# SunlightDetector.net
KiCad netlist of a schematic drawn in EAGLE
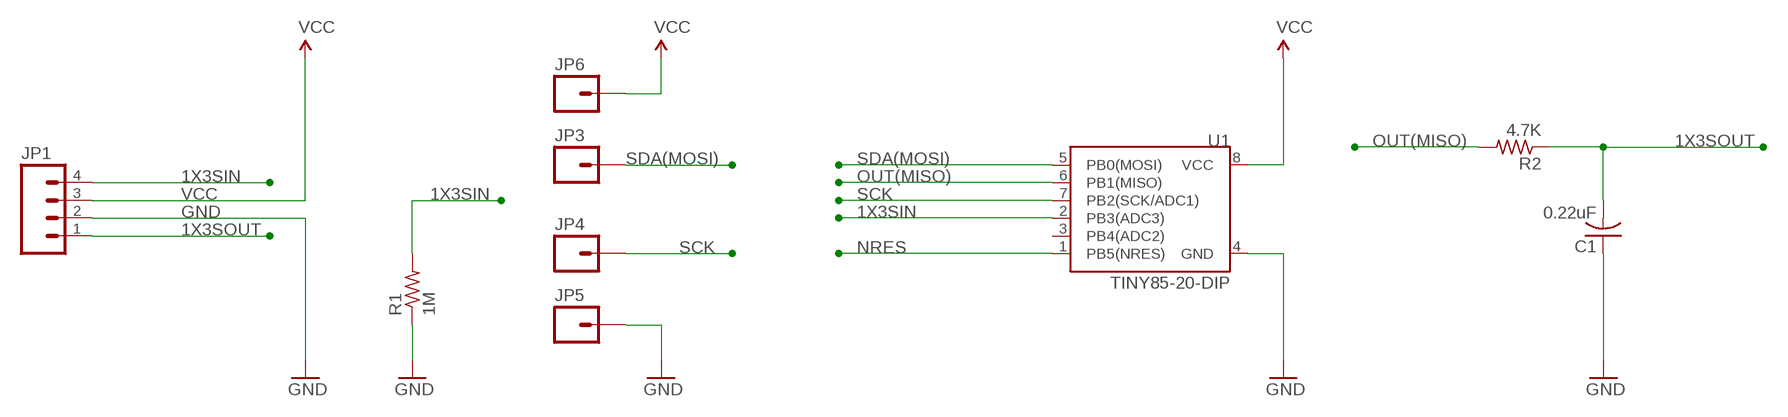
[diagram p0: schematic, sheet 1]

(export (version "E")
  (design (tool "Eeschema 10.0.6"))
  (components
    (comp (ref "C1")
      (value "0.22uF")
      (footprint "eagle-import:C0402")
      (libsource (lib "eagle-import") (part "C-USC0402"))
    )
    (comp (ref "JP1")
      (value "M04PTH")
      (footprint "eagle-import:1X04")
      (libsource (lib "eagle-import") (part "M04PTH"))
    )
    (comp (ref "JP3")
      (value "M01PTH")
      (footprint "eagle-import:1X01")
      (libsource (lib "eagle-import") (part "M01PTH"))
    )
    (comp (ref "JP4")
      (value "M01PTH")
      (footprint "eagle-import:1X01")
      (libsource (lib "eagle-import") (part "M01PTH"))
    )
    (comp (ref "JP5")
      (value "M01PTH")
      (footprint "eagle-import:1X01")
      (libsource (lib "eagle-import") (part "M01PTH"))
    )
    (comp (ref "JP6")
      (value "M01PTH")
      (footprint "eagle-import:1X01")
      (libsource (lib "eagle-import") (part "M01PTH"))
    )
    (comp (ref "R1")
      (value "1M")
      (footprint "eagle-import:R0603")
      (libsource (lib "eagle-import") (part "R-US_R0603"))
    )
    (comp (ref "R2")
      (value "4.7K")
      (footprint "eagle-import:R0603")
      (libsource (lib "eagle-import") (part "R-US_R0603"))
    )
    (comp (ref "U1")
      (value "TINY85-20-DIP")
      (footprint "eagle-import:DIP08")
      (libsource (lib "eagle-import") (part "ATTINY45TINY85-20-DIP"))
    )
  )
  (nets
    (net (code "1") (name "/1X3SIN") (class "Default")
      (node (ref "JP1") (pin "4") (pinfunction "4_4") (pintype "passive"))
      (node (ref "R1") (pin "2") (pinfunction "2_2") (pintype "passive"))
      (node (ref "U1") (pin "2") (pinfunction "PB3(ADC3)_2") (pintype "bidirectional"))
    )
    (net (code "2") (name "/1X3SOUT") (class "Default")
      (node (ref "C1") (pin "2") (pinfunction "2_2") (pintype "passive"))
      (node (ref "JP1") (pin "1") (pinfunction "1_1") (pintype "passive"))
      (node (ref "R2") (pin "1") (pinfunction "1_1") (pintype "passive"))
    )
    (net (code "3") (name "/NRES") (class "Default")
      (node (ref "U1") (pin "1") (pinfunction "PB5(NRES)_1") (pintype "bidirectional"))
    )
    (net (code "4") (name "/OUT(MISO)") (class "Default")
      (node (ref "R2") (pin "2") (pinfunction "2_2") (pintype "passive"))
      (node (ref "U1") (pin "6") (pinfunction "PB1(MISO)_6") (pintype "bidirectional"))
    )
    (net (code "5") (name "/SCK") (class "Default")
      (node (ref "JP4") (pin "1") (pinfunction "1_1") (pintype "passive"))
      (node (ref "U1") (pin "7") (pinfunction "PB2(SCK/ADC1)_7") (pintype "bidirectional"))
    )
    (net (code "6") (name "/SDA(MOSI)") (class "Default")
      (node (ref "JP3") (pin "1") (pinfunction "1_1") (pintype "passive"))
      (node (ref "U1") (pin "5") (pinfunction "PB0(MOSI)_5") (pintype "bidirectional"))
    )
    (net (code "7") (name "GND") (class "Default")
      (node (ref "C1") (pin "1") (pinfunction "1_1") (pintype "passive"))
      (node (ref "JP1") (pin "2") (pinfunction "2_2") (pintype "passive"))
      (node (ref "JP5") (pin "1") (pinfunction "1_1") (pintype "passive"))
      (node (ref "R1") (pin "1") (pinfunction "1_1") (pintype "passive"))
      (node (ref "U1") (pin "4") (pinfunction "GND_4") (pintype "bidirectional"))
    )
    (net (code "8") (name "VCC") (class "Default")
      (node (ref "JP1") (pin "3") (pinfunction "3_3") (pintype "passive"))
      (node (ref "JP6") (pin "1") (pinfunction "1_1") (pintype "passive"))
      (node (ref "U1") (pin "8") (pinfunction "VCC_8") (pintype "bidirectional"))
    )
    (net (code "9") (name "unconnected-(U1-PB4(ADC2)-Pad3)") (class "Default")
      (node (ref "U1") (pin "3") (pinfunction "PB4(ADC2)_3") (pintype "bidirectional"))
    )
  )
)
